# Measuring_distance_ultrasonic_Sheet.net
KiCad netlist of a schematic drawn in Altium Designer
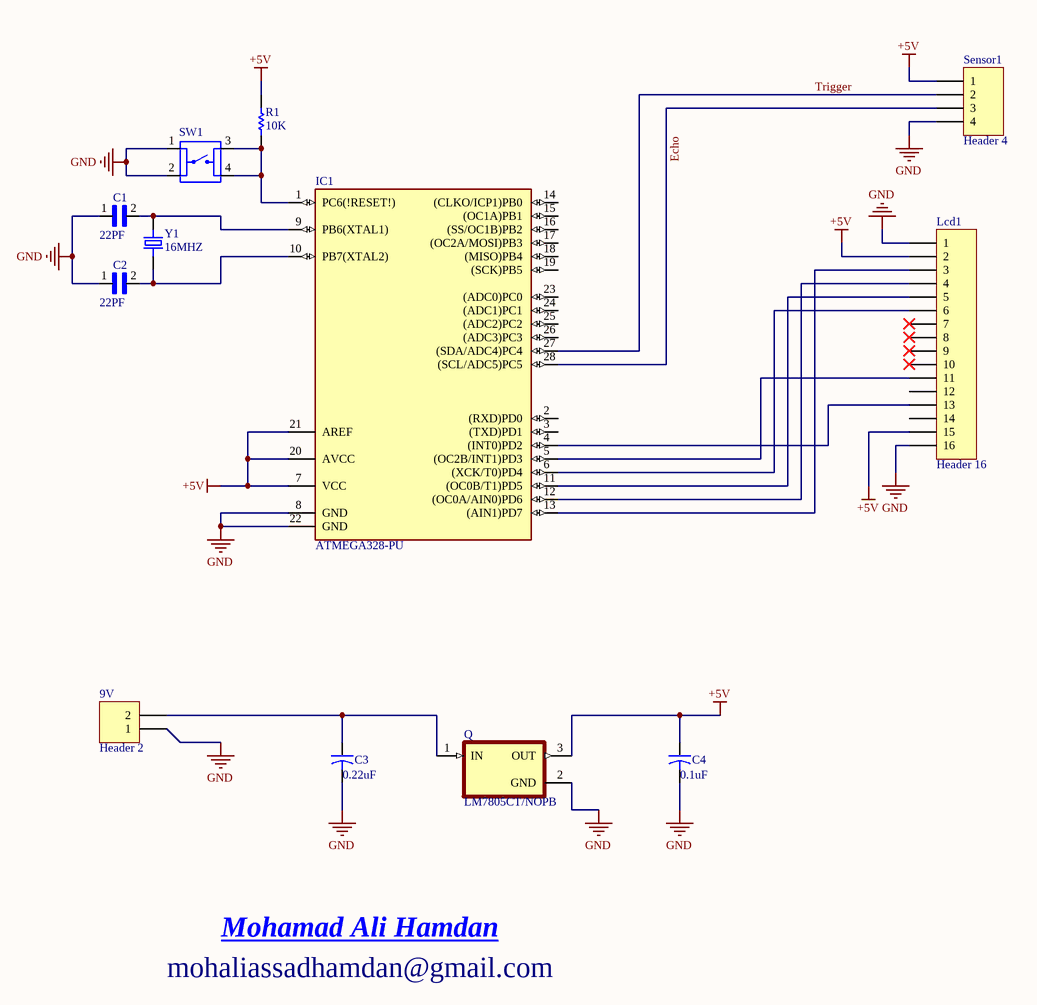
[diagram p0: Measuring_distance_ultrasonic_Sheet.SchDoc]

(export (version "E")
  (design (tool "Eeschema 10.0.6"))
  (components
    (comp (ref "9V")
      (value "Header 2")
      (footprint "Connector_green_2pins")
      (description "Header, 2-Pin")
      (fields (field (name "PUBLISHER") "Altium Limited"))
      (libsource (lib "Miscellaneous Connectors") (part "Header 2"))
    )
    (comp (ref "C1")
      (value "14pF")
      (footprint "CAP_RDER71H333K0M1H03A")
      (description "Lead capacitor X7R(EIA) with Capacitance 33000pF, Rated Voltage 50Vdc")
      (fields
        (field (name "MF") "Murata")
        (field (name "MP") "RDER71H333K0M1H03A")
        (field (name "BUYPART") "22PF")
      )
      (libsource (lib "RDER71H333K0M1H03A") (part "RDER71H333K0M1H03A"))
    )
    (comp (ref "C2")
      (value "14pF")
      (footprint "CAP_RDER71H333K0M1H03A")
      (description "Lead capacitor X7R(EIA) with Capacitance 33000pF, Rated Voltage 50Vdc")
      (fields
        (field (name "MF") "Murata")
        (field (name "MP") "RDER71H333K0M1H03A")
        (field (name "BUYPART") "22PF")
      )
      (libsource (lib "RDER71H333K0M1H03A") (part "RDER71H333K0M1H03A"))
    )
    (comp (ref "C3")
      (value "0.22uF")
      (footprint "Capacitor_polarized_100uF")
      (description "Capacitor")
      (fields (field (name "Comment") "Cap2") (field (name "PUBLISHER") "Altium Limited"))
      (libsource (lib "Miscellaneous Devices") (part "Cap2"))
    )
    (comp (ref "C4")
      (value "0.1uF")
      (footprint "Capacitor_polarized_100uF")
      (description "Capacitor")
      (fields (field (name "Comment") "Cap2") (field (name "PUBLISHER") "Altium Limited"))
      (libsource (lib "Miscellaneous Devices") (part "Cap2"))
    )
    (comp (ref "IC1")
      (value "ATMEGA328-PU")
      (footprint "Atmega:DIL28")
      (description "AVR AVRÂ® ATmega Microcontroller IC 8-Bit 20MHz 32KB _16K x 16_ FLASH 28-PDIP")
      (fields (field (name "MF") "Microchip Technology"))
      (libsource (lib "Atmega328PU") (part "ATMEGA328-PU"))
    )
    (comp (ref "Lcd1")
      (value "Header 16")
      (footprint "LCD_16_2")
      (description "Header, 16-Pin")
      (fields (field (name "PUBLISHER") "Altium Limited"))
      (libsource (lib "Miscellaneous Connectors") (part "Header 16"))
    )
    (comp (ref "Q")
      (value "LM7805CT/NOPB")
      (footprint "LM7805")
      (description "Linear Voltage Regulator IC 1 Output 1A TO-220-3")
      (fields (field (name "MP") "LM7805CT") (field (name "MF") "ON Semiconductor"))
      (libsource (lib "7805") (part "LM7805CT/NOPB"))
    )
    (comp (ref "R1")
      (value "10K")
      (footprint "resistor")
      (description "Resistor")
      (fields (field (name "Comment") "Res1") (field (name "PUBLISHER") "Altium Limited"))
      (libsource (lib "Miscellaneous Devices") (part "Res1"))
    )
    (comp (ref "Sensor1")
      (value "Header 4")
      (footprint "header_4")
      (description "Header, 4-Pin")
      (fields (field (name "PUBLISHER") "Altium Limited"))
      (libsource (lib "Miscellaneous Connectors") (part "Header 4"))
    )
    (comp (ref "SW1")
      (value "FSM8JH")
      (footprint "SW_FSM8JH")
      (description "Tactile Switch SPST-NO Top Actuated Through Hole")
      (fields (field (name "MF") "TE Connectivity"))
      (libsource (lib "switch") (part "FSM8JH"))
    )
    (comp (ref "Y1")
      (value "16MHZ")
      (footprint "XTAL_ECS-160-20-4VX")
      (description "16MHz Â±30ppm Crystal 20pF 50 Ohms HC-49/US")
      (fields (field (name "MF") "ECS Inc.") (field (name "MP") "ECS-160-20-4VX"))
      (libsource (lib "Crystal") (part "ECS-160-20-4VX"))
    )
  )
  (nets
    (net (code "1") (name "+5V") (class "Default")
      (node (ref "C4") (pin "1") (pinfunction "1_1") (pintype "passive"))
      (node (ref "IC1") (pin "20") (pinfunction "AVCC_20") (pintype "power_in"))
      (node (ref "IC1") (pin "21") (pinfunction "AREF_21") (pintype "passive"))
      (node (ref "IC1") (pin "7") (pinfunction "VCC_7") (pintype "power_in"))
      (node (ref "Lcd1") (pin "15") (pinfunction "15_15") (pintype "passive"))
      (node (ref "Lcd1") (pin "2") (pinfunction "2_2") (pintype "passive"))
      (node (ref "Q") (pin "3") (pinfunction "OUT_3") (pintype "output"))
      (node (ref "R1") (pin "2") (pinfunction "2_2") (pintype "passive"))
      (node (ref "Sensor1") (pin "1") (pinfunction "1_1") (pintype "passive"))
    )
    (net (code "2") (name "/Echo") (class "Default")
      (node (ref "IC1") (pin "28") (pinfunction "(SCL/ADC5)PC5_28") (pintype "bidirectional"))
      (node (ref "Sensor1") (pin "3") (pinfunction "3_3") (pintype "passive"))
    )
    (net (code "3") (name "/Trigger") (class "Default")
      (node (ref "IC1") (pin "27") (pinfunction "(SDA/ADC4)PC4_27") (pintype "bidirectional"))
      (node (ref "Sensor1") (pin "2") (pinfunction "2_2") (pintype "passive"))
    )
    (net (code "4") (name "GND") (class "Default")
      (node (ref "9V") (pin "1") (pinfunction "1_1") (pintype "passive"))
      (node (ref "C1") (pin "1") (pinfunction "1_1") (pintype "passive"))
      (node (ref "C2") (pin "1") (pinfunction "1_1") (pintype "passive"))
      (node (ref "C3") (pin "2") (pinfunction "2_2") (pintype "passive"))
      (node (ref "C4") (pin "2") (pinfunction "2_2") (pintype "passive"))
      (node (ref "IC1") (pin "22") (pinfunction "GND_22") (pintype "power_in"))
      (node (ref "IC1") (pin "8") (pinfunction "GND_8") (pintype "power_in"))
      (node (ref "Lcd1") (pin "1") (pinfunction "1_1") (pintype "passive"))
      (node (ref "Lcd1") (pin "16") (pinfunction "16_16") (pintype "passive"))
      (node (ref "Q") (pin "2") (pinfunction "GND_2") (pintype "power_in"))
      (node (ref "SW1") (pin "1") (pinfunction "1_1") (pintype "passive"))
      (node (ref "SW1") (pin "2") (pinfunction "2_2") (pintype "passive"))
      (node (ref "Sensor1") (pin "4") (pinfunction "4_4") (pintype "passive"))
    )
    (net (code "5") (name "Net-(IC1-(AIN1)PD7)") (class "Default")
      (node (ref "IC1") (pin "13") (pinfunction "(AIN1)PD7_13") (pintype "bidirectional"))
      (node (ref "Lcd1") (pin "3") (pinfunction "3_3") (pintype "passive"))
    )
    (net (code "6") (name "Net-(IC1-(INT0)PD2)") (class "Default")
      (node (ref "IC1") (pin "4") (pinfunction "(INT0)PD2_4") (pintype "bidirectional"))
      (node (ref "Lcd1") (pin "13") (pinfunction "13_13") (pintype "passive"))
    )
    (net (code "7") (name "Net-(IC1-(OC0A{slash}AIN0)PD6)") (class "Default")
      (node (ref "IC1") (pin "12") (pinfunction "(OC0A/AIN0)PD6_12") (pintype "bidirectional"))
      (node (ref "Lcd1") (pin "4") (pinfunction "4_4") (pintype "passive"))
    )
    (net (code "8") (name "Net-(IC1-(OC0B{slash}T1)PD5)") (class "Default")
      (node (ref "IC1") (pin "11") (pinfunction "(OC0B/T1)PD5_11") (pintype "bidirectional"))
      (node (ref "Lcd1") (pin "5") (pinfunction "5_5") (pintype "passive"))
    )
    (net (code "9") (name "Net-(IC1-(OC2B{slash}INT1)PD3)") (class "Default")
      (node (ref "IC1") (pin "5") (pinfunction "(OC2B/INT1)PD3_5") (pintype "bidirectional"))
      (node (ref "Lcd1") (pin "11") (pinfunction "11_11") (pintype "passive"))
    )
    (net (code "10") (name "Net-(IC1-(XCK{slash}T0)PD4)") (class "Default")
      (node (ref "IC1") (pin "6") (pinfunction "(XCK/T0)PD4_6") (pintype "bidirectional"))
      (node (ref "Lcd1") (pin "6") (pinfunction "6_6") (pintype "passive"))
    )
    (net (code "11") (name "Net-(IC1-PB6(XTAL1))") (class "Default")
      (node (ref "C1") (pin "2") (pinfunction "2_2") (pintype "passive"))
      (node (ref "IC1") (pin "9") (pinfunction "PB6(XTAL1)_9") (pintype "bidirectional"))
      (node (ref "Y1") (pin "2") (pinfunction "2_2") (pintype "passive"))
    )
    (net (code "12") (name "Net-(IC1-PB7(XTAL2))") (class "Default")
      (node (ref "C2") (pin "2") (pinfunction "2_2") (pintype "passive"))
      (node (ref "IC1") (pin "10") (pinfunction "PB7(XTAL2)_10") (pintype "bidirectional"))
      (node (ref "Y1") (pin "1") (pinfunction "1_1") (pintype "passive"))
    )
    (net (code "13") (name "Net-(IC1-PC6(!RESET!))") (class "Default")
      (node (ref "IC1") (pin "1") (pinfunction "PC6(!RESET!)_1") (pintype "bidirectional"))
      (node (ref "R1") (pin "1") (pinfunction "1_1") (pintype "passive"))
      (node (ref "SW1") (pin "3") (pinfunction "3_3") (pintype "passive"))
      (node (ref "SW1") (pin "4") (pinfunction "4_4") (pintype "passive"))
    )
    (net (code "14") (name "Net-(Q-IN)") (class "Default")
      (node (ref "9V") (pin "2") (pinfunction "2_2") (pintype "passive"))
      (node (ref "C3") (pin "1") (pinfunction "1_1") (pintype "passive"))
      (node (ref "Q") (pin "1") (pinfunction "IN_1") (pintype "input"))
    )
    (net (code "15") (name "unconnected-(IC1-(ADC0)PC0-Pad23)") (class "Default")
      (node (ref "IC1") (pin "23") (pinfunction "(ADC0)PC0_23") (pintype "bidirectional"))
    )
    (net (code "16") (name "unconnected-(IC1-(ADC1)PC1-Pad24)") (class "Default")
      (node (ref "IC1") (pin "24") (pinfunction "(ADC1)PC1_24") (pintype "bidirectional"))
    )
    (net (code "17") (name "unconnected-(IC1-(ADC2)PC2-Pad25)") (class "Default")
      (node (ref "IC1") (pin "25") (pinfunction "(ADC2)PC2_25") (pintype "bidirectional"))
    )
    (net (code "18") (name "unconnected-(IC1-(ADC3)PC3-Pad26)") (class "Default")
      (node (ref "IC1") (pin "26") (pinfunction "(ADC3)PC3_26") (pintype "bidirectional"))
    )
    (net (code "19") (name "unconnected-(IC1-(CLKO{slash}ICP1)PB0-Pad14)") (class "Default")
      (node (ref "IC1") (pin "14") (pinfunction "(CLKO/ICP1)PB0_14") (pintype "bidirectional"))
    )
    (net (code "20") (name "unconnected-(IC1-(MISO)PB4-Pad18)") (class "Default")
      (node (ref "IC1") (pin "18") (pinfunction "(MISO)PB4_18") (pintype "bidirectional"))
    )
    (net (code "21") (name "unconnected-(IC1-(OC1A)PB1-Pad15)") (class "Default")
      (node (ref "IC1") (pin "15") (pinfunction "(OC1A)PB1_15") (pintype "bidirectional"))
    )
    (net (code "22") (name "unconnected-(IC1-(OC2A{slash}MOSI)PB3-Pad17)") (class "Default")
      (node (ref "IC1") (pin "17") (pinfunction "(OC2A/MOSI)PB3_17") (pintype "bidirectional"))
    )
    (net (code "23") (name "unconnected-(IC1-(RXD)PD0-Pad2)") (class "Default")
      (node (ref "IC1") (pin "2") (pinfunction "(RXD)PD0_2") (pintype "bidirectional"))
    )
    (net (code "24") (name "unconnected-(IC1-(SCK)PB5-Pad19)") (class "Default")
      (node (ref "IC1") (pin "19") (pinfunction "(SCK)PB5_19") (pintype "bidirectional"))
    )
    (net (code "25") (name "unconnected-(IC1-(SS{slash}OC1B)PB2-Pad16)") (class "Default")
      (node (ref "IC1") (pin "16") (pinfunction "(SS/OC1B)PB2_16") (pintype "bidirectional"))
    )
    (net (code "26") (name "unconnected-(IC1-(TXD)PD1-Pad3)") (class "Default")
      (node (ref "IC1") (pin "3") (pinfunction "(TXD)PD1_3") (pintype "bidirectional"))
    )
    (net (code "27") (name "unconnected-(Lcd1-Pad7)") (class "Default")
      (node (ref "Lcd1") (pin "7") (pinfunction "7_7") (pintype "passive+no_connect"))
    )
    (net (code "28") (name "unconnected-(Lcd1-Pad8)") (class "Default")
      (node (ref "Lcd1") (pin "8") (pinfunction "8_8") (pintype "passive+no_connect"))
    )
    (net (code "29") (name "unconnected-(Lcd1-Pad9)") (class "Default")
      (node (ref "Lcd1") (pin "9") (pinfunction "9_9") (pintype "passive+no_connect"))
    )
    (net (code "30") (name "unconnected-(Lcd1-Pad10)") (class "Default")
      (node (ref "Lcd1") (pin "10") (pinfunction "10_10") (pintype "passive+no_connect"))
    )
    (net (code "31") (name "unconnected-(Lcd1-Pad12)") (class "Default")
      (node (ref "Lcd1") (pin "12") (pinfunction "12_12") (pintype "passive"))
    )
    (net (code "32") (name "unconnected-(Lcd1-Pad14)") (class "Default")
      (node (ref "Lcd1") (pin "14") (pinfunction "14_14") (pintype "passive"))
    )
  )
)
